# usart_irq.net
KiCad netlist of a schematic drawn in EAGLE
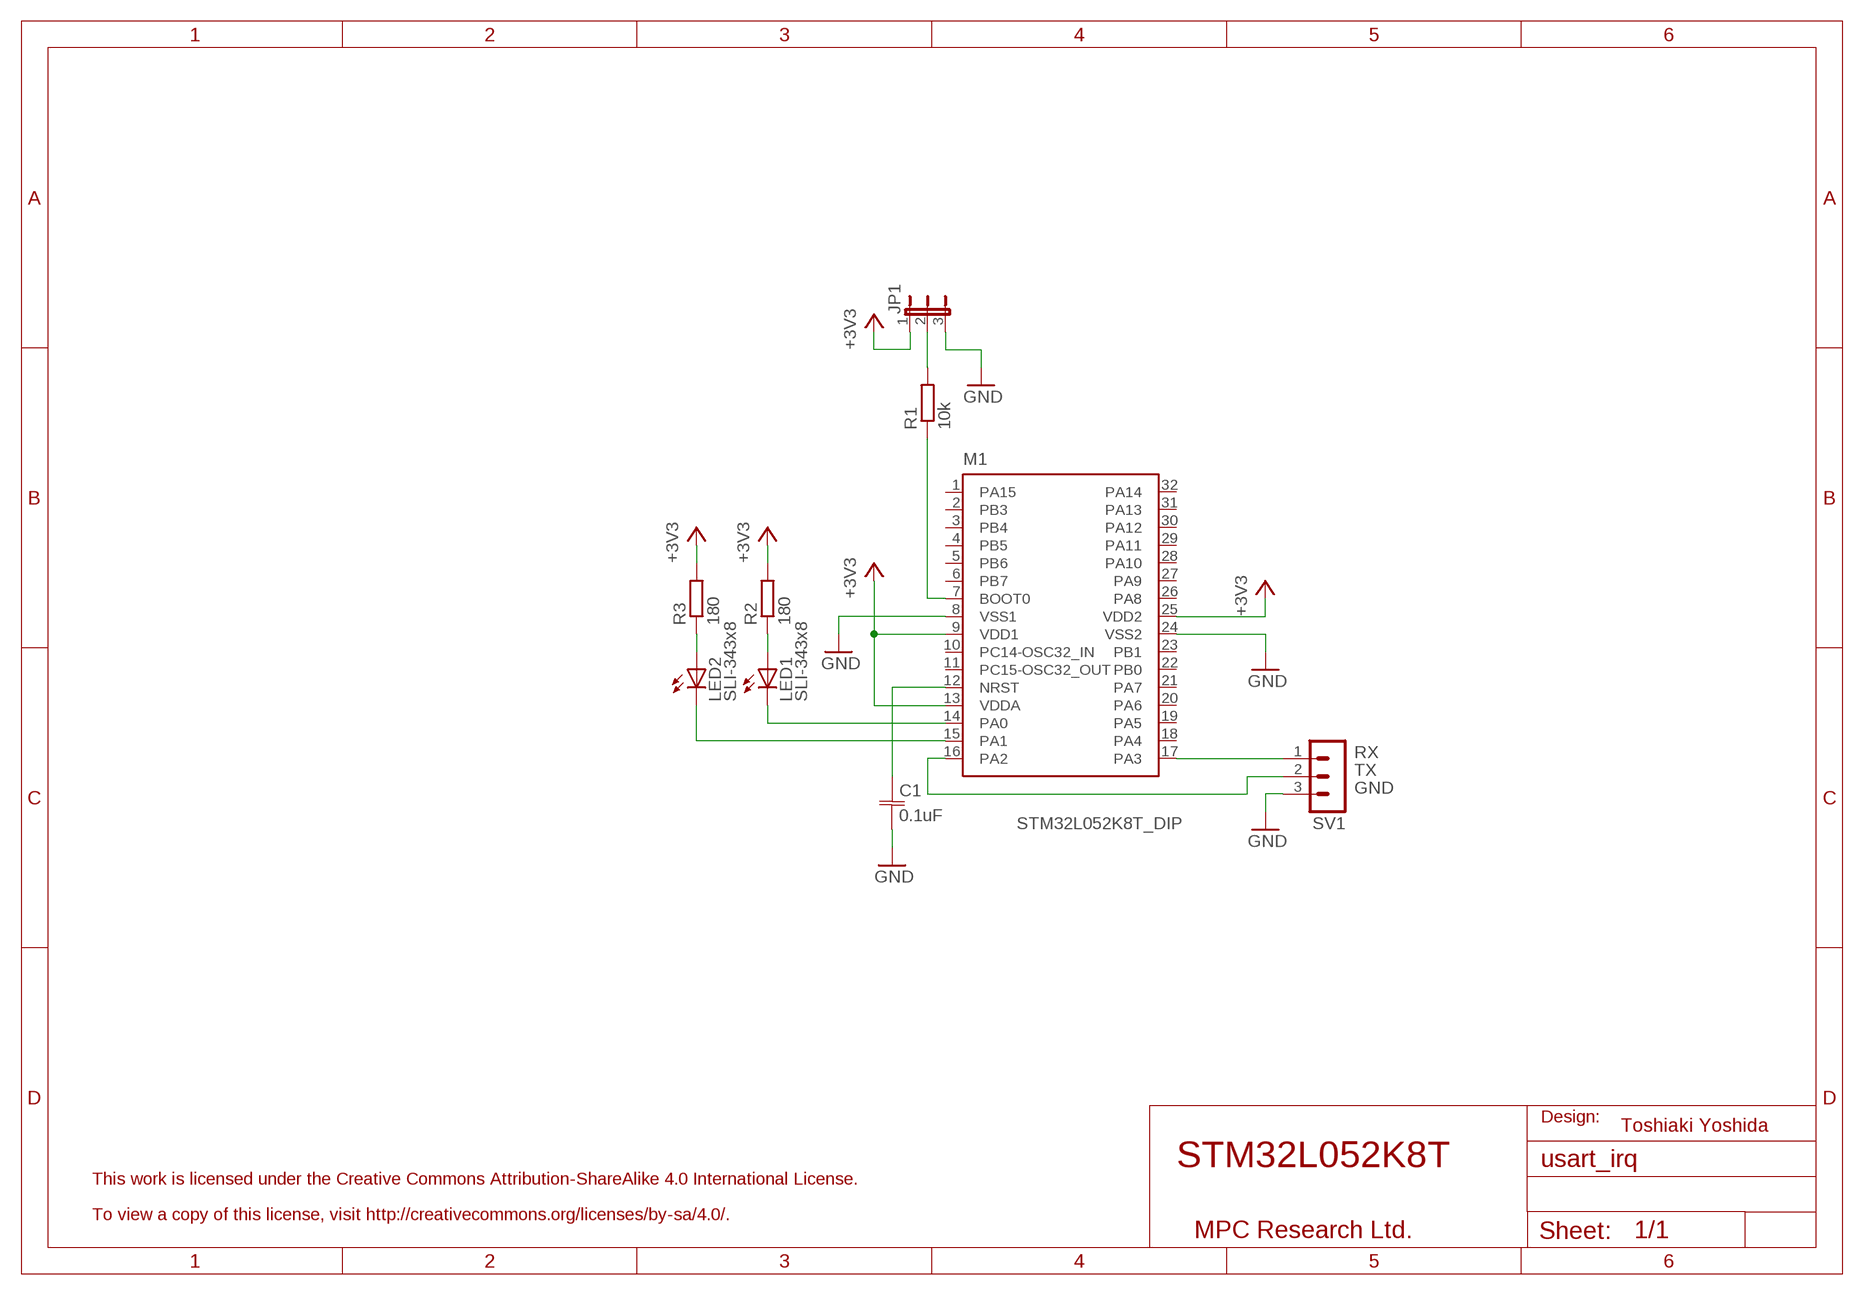
[diagram p0: schematic, sheet 1]

(export (version "E")
  (design (tool "Eeschema 10.0.6"))
  (components
    (comp (ref "C1")
      (value "0.1uF")
      (footprint "eagle-import:C050-024X044")
      (libsource (lib "eagle-import") (part "C-JIS050-024X044"))
    )
    (comp (ref "JP1")
      (value "JP2E")
      (footprint "eagle-import:JP2")
      (libsource (lib "eagle-import") (part "JP2E"))
    )
    (comp (ref "LED1")
      (value "SLI-343x8")
      (footprint "eagle-import:LED3MM")
      (libsource (lib "eagle-import") (part "LED3MM"))
    )
    (comp (ref "LED2")
      (value "SLI-343x8")
      (footprint "eagle-import:LED3MM")
      (libsource (lib "eagle-import") (part "LED3MM"))
    )
    (comp (ref "M1")
      (value "STM32L052K8T_DIP")
      (footprint "eagle-import:DIP32")
      (libsource (lib "eagle-import") (part "STM32L052K8T_DIP"))
    )
    (comp (ref "R1")
      (value "10k")
      (footprint "eagle-import:0207_2V")
      (libsource (lib "eagle-import") (part "R-EU_0207/2V"))
    )
    (comp (ref "R2")
      (value "180")
      (footprint "eagle-import:0207_2V")
      (libsource (lib "eagle-import") (part "R-EU_0207/2V"))
    )
    (comp (ref "R3")
      (value "180")
      (footprint "eagle-import:0207_2V")
      (libsource (lib "eagle-import") (part "R-EU_0207/2V"))
    )
    (comp (ref "SV1")
      (value "MA03-1")
      (footprint "eagle-import:MA03-1")
      (libsource (lib "eagle-import") (part "MA03-1"))
    )
  )
  (nets
    (net (code "1") (name "+3V3") (class "Default")
      (node (ref "JP1") (pin "1") (pinfunction "1_1") (pintype "passive"))
      (node (ref "M1") (pin "13") (pinfunction "VDDA_13") (pintype "power_in"))
      (node (ref "M1") (pin "25") (pinfunction "VDD2_25") (pintype "bidirectional"))
      (node (ref "M1") (pin "9") (pinfunction "VDD1_9") (pintype "power_in"))
      (node (ref "R2") (pin "2") (pinfunction "2_2") (pintype "passive"))
      (node (ref "R3") (pin "2") (pinfunction "2_2") (pintype "passive"))
    )
    (net (code "2") (name "GND") (class "Default")
      (node (ref "C1") (pin "2") (pinfunction "2_2") (pintype "passive"))
      (node (ref "JP1") (pin "3") (pinfunction "3_3") (pintype "passive"))
      (node (ref "M1") (pin "24") (pinfunction "VSS2_24") (pintype "power_in"))
      (node (ref "M1") (pin "8") (pinfunction "VSS1_8") (pintype "power_in"))
      (node (ref "SV1") (pin "3") (pinfunction "3_3") (pintype "passive"))
    )
    (net (code "3") (name "Net-(JP1-Pad2)") (class "Default")
      (node (ref "JP1") (pin "2") (pinfunction "2_2") (pintype "passive"))
      (node (ref "R1") (pin "2") (pinfunction "2_2") (pintype "passive"))
    )
    (net (code "4") (name "Net-(LED1-C)") (class "Default")
      (node (ref "LED1") (pin "K") (pinfunction "C_K") (pintype "passive"))
      (node (ref "M1") (pin "14") (pinfunction "PA0_14") (pintype "bidirectional"))
    )
    (net (code "5") (name "Net-(LED1-PadA)") (class "Default")
      (node (ref "LED1") (pin "A") (pinfunction "A_A") (pintype "passive"))
      (node (ref "R2") (pin "1") (pinfunction "1_1") (pintype "passive"))
    )
    (net (code "6") (name "Net-(LED2-C)") (class "Default")
      (node (ref "LED2") (pin "K") (pinfunction "C_K") (pintype "passive"))
      (node (ref "M1") (pin "15") (pinfunction "PA1_15") (pintype "bidirectional"))
    )
    (net (code "7") (name "Net-(LED2-PadA)") (class "Default")
      (node (ref "LED2") (pin "A") (pinfunction "A_A") (pintype "passive"))
      (node (ref "R3") (pin "1") (pinfunction "1_1") (pintype "passive"))
    )
    (net (code "8") (name "Net-(M1-BOOT0)") (class "Default")
      (node (ref "M1") (pin "7") (pinfunction "BOOT0_7") (pintype "bidirectional"))
      (node (ref "R1") (pin "1") (pinfunction "1_1") (pintype "passive"))
    )
    (net (code "9") (name "Net-(M1-NRST)") (class "Default")
      (node (ref "C1") (pin "1") (pinfunction "1_1") (pintype "passive"))
      (node (ref "M1") (pin "12") (pinfunction "NRST_12") (pintype "bidirectional"))
    )
    (net (code "10") (name "Net-(M1-PA2)") (class "Default")
      (node (ref "M1") (pin "16") (pinfunction "PA2_16") (pintype "bidirectional"))
      (node (ref "SV1") (pin "2") (pinfunction "2_2") (pintype "passive"))
    )
    (net (code "11") (name "Net-(M1-PA3)") (class "Default")
      (node (ref "M1") (pin "17") (pinfunction "PA3_17") (pintype "bidirectional"))
      (node (ref "SV1") (pin "1") (pinfunction "1_1") (pintype "passive"))
    )
    (net (code "12") (name "unconnected-(M1-PA4-Pad18)") (class "Default")
      (node (ref "M1") (pin "18") (pinfunction "PA4_18") (pintype "bidirectional"))
    )
    (net (code "13") (name "unconnected-(M1-PA5-Pad19)") (class "Default")
      (node (ref "M1") (pin "19") (pinfunction "PA5_19") (pintype "bidirectional"))
    )
    (net (code "14") (name "unconnected-(M1-PA6-Pad20)") (class "Default")
      (node (ref "M1") (pin "20") (pinfunction "PA6_20") (pintype "bidirectional"))
    )
    (net (code "15") (name "unconnected-(M1-PA7-Pad21)") (class "Default")
      (node (ref "M1") (pin "21") (pinfunction "PA7_21") (pintype "bidirectional"))
    )
    (net (code "16") (name "unconnected-(M1-PA8-Pad26)") (class "Default")
      (node (ref "M1") (pin "26") (pinfunction "PA8_26") (pintype "bidirectional"))
    )
    (net (code "17") (name "unconnected-(M1-PA9-Pad27)") (class "Default")
      (node (ref "M1") (pin "27") (pinfunction "PA9_27") (pintype "bidirectional"))
    )
    (net (code "18") (name "unconnected-(M1-PA10-Pad28)") (class "Default")
      (node (ref "M1") (pin "28") (pinfunction "PA10_28") (pintype "bidirectional"))
    )
    (net (code "19") (name "unconnected-(M1-PA11-Pad29)") (class "Default")
      (node (ref "M1") (pin "29") (pinfunction "PA11_29") (pintype "bidirectional"))
    )
    (net (code "20") (name "unconnected-(M1-PA12-Pad30)") (class "Default")
      (node (ref "M1") (pin "30") (pinfunction "PA12_30") (pintype "bidirectional"))
    )
    (net (code "21") (name "unconnected-(M1-PA13-Pad31)") (class "Default")
      (node (ref "M1") (pin "31") (pinfunction "PA13_31") (pintype "bidirectional"))
    )
    (net (code "22") (name "unconnected-(M1-PA14-Pad32)") (class "Default")
      (node (ref "M1") (pin "32") (pinfunction "PA14_32") (pintype "bidirectional"))
    )
    (net (code "23") (name "unconnected-(M1-PA15-Pad1)") (class "Default")
      (node (ref "M1") (pin "1") (pinfunction "PA15_1") (pintype "bidirectional"))
    )
    (net (code "24") (name "unconnected-(M1-PB0-Pad22)") (class "Default")
      (node (ref "M1") (pin "22") (pinfunction "PB0_22") (pintype "bidirectional"))
    )
    (net (code "25") (name "unconnected-(M1-PB1-Pad23)") (class "Default")
      (node (ref "M1") (pin "23") (pinfunction "PB1_23") (pintype "bidirectional"))
    )
    (net (code "26") (name "unconnected-(M1-PB3-Pad2)") (class "Default")
      (node (ref "M1") (pin "2") (pinfunction "PB3_2") (pintype "bidirectional"))
    )
    (net (code "27") (name "unconnected-(M1-PB4-Pad3)") (class "Default")
      (node (ref "M1") (pin "3") (pinfunction "PB4_3") (pintype "bidirectional"))
    )
    (net (code "28") (name "unconnected-(M1-PB5-Pad4)") (class "Default")
      (node (ref "M1") (pin "4") (pinfunction "PB5_4") (pintype "bidirectional"))
    )
    (net (code "29") (name "unconnected-(M1-PB6-Pad5)") (class "Default")
      (node (ref "M1") (pin "5") (pinfunction "PB6_5") (pintype "bidirectional"))
    )
    (net (code "30") (name "unconnected-(M1-PB7-Pad6)") (class "Default")
      (node (ref "M1") (pin "6") (pinfunction "PB7_6") (pintype "bidirectional"))
    )
    (net (code "31") (name "unconnected-(M1-PC14-OSC32_IN-Pad10)") (class "Default")
      (node (ref "M1") (pin "10") (pinfunction "PC14-OSC32_IN_10") (pintype "bidirectional"))
    )
    (net (code "32") (name "unconnected-(M1-PC15-OSC32_OUT-Pad11)") (class "Default")
      (node (ref "M1") (pin "11") (pinfunction "PC15-OSC32_OUT_11") (pintype "bidirectional"))
    )
  )
)
